# kbd_training.net
KiCad netlist of a schematic drawn in Altium Designer
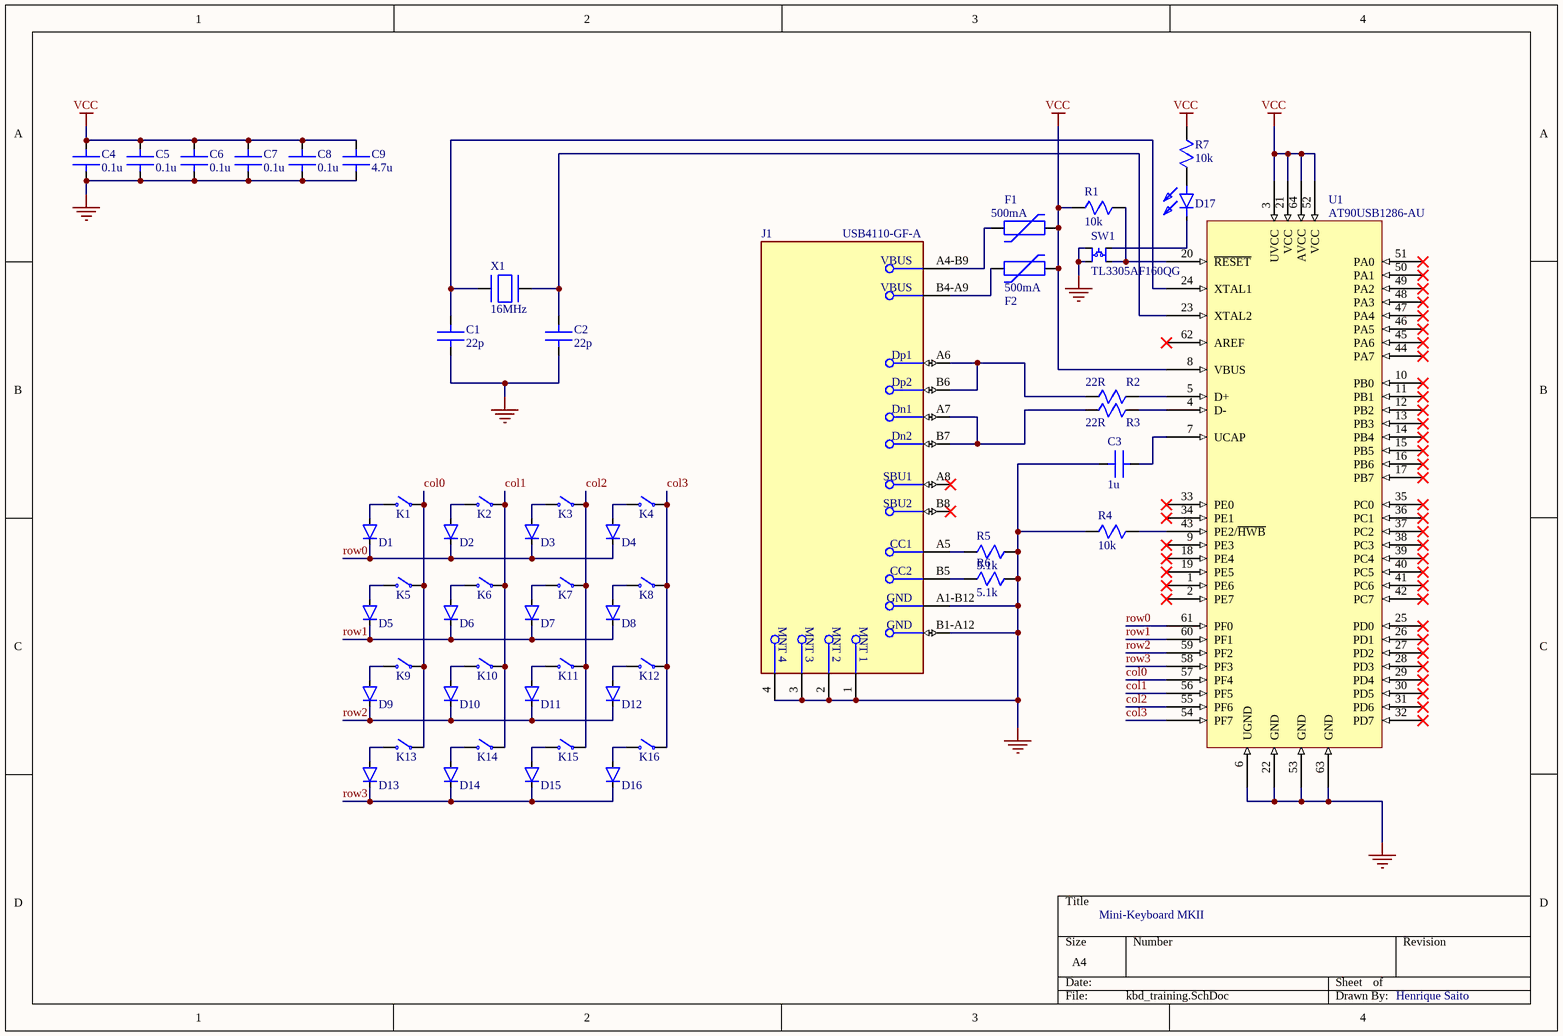
[diagram p0: kbd_training.SchDoc]

(export (version "E")
  (design (tool "Eeschema 10.0.6"))
  (components
    (comp (ref "C1")
      (value "22p")
      (footprint "Cap0805")
      (description "Cap Ceramic 22pF 50V C0G 5% SMD 0805 125C Plastic T/R")
      (fields
        (field (name "MANUFACTURER") "KEMET")
        (field (name "MANUFACTURER PART NUMBER") "C0805C220J5GACTU")
      )
      (libsource (lib "kbd_training_sch_lib") (part "C0805C220J5GACTU"))
    )
    (comp (ref "C2")
      (value "22p")
      (footprint "Cap0805")
      (description "Cap Ceramic 22pF 50V C0G 5% SMD 0805 125C Plastic T/R")
      (fields
        (field (name "MANUFACTURER") "KEMET")
        (field (name "MANUFACTURER PART NUMBER") "C0805C220J5GACTU")
      )
      (libsource (lib "kbd_training_sch_lib") (part "C0805C220J5GACTU"))
    )
    (comp (ref "C3")
      (value "1u")
      (footprint "Cap0805")
      (description "Cap, 1ΜF, 16V, 10%, X7R, 0805")
      (fields
        (field (name "MANUFACTURER") "Wurth Electronics")
        (field (name "MANUFACTURER PART NUMBER") "885012207051")
      )
      (libsource (lib "kbd_training_sch_lib") (part "885012207051"))
    )
    (comp (ref "C4")
      (value "0.1u")
      (footprint "Cap0805")
      (description "Cap Ceramic 0.1uF 50V Y5V -20% to 80% SMD 0805 85C T/R")
      (fields
        (field (name "MANUFACTURER") "Yageo")
        (field (name "MANUFACTURER PART NUMBER") "CC0805ZRY5V9BB104")
      )
      (libsource (lib "kbd_training_sch_lib") (part "CC0805ZRY5V9BB104"))
    )
    (comp (ref "C5")
      (value "0.1u")
      (footprint "Cap0805")
      (description "Cap Ceramic 0.1uF 50V Y5V -20% to 80% SMD 0805 85C T/R")
      (fields
        (field (name "MANUFACTURER") "Yageo")
        (field (name "MANUFACTURER PART NUMBER") "CC0805ZRY5V9BB104")
      )
      (libsource (lib "kbd_training_sch_lib") (part "CC0805ZRY5V9BB104"))
    )
    (comp (ref "C6")
      (value "0.1u")
      (footprint "Cap0805")
      (description "Cap Ceramic 0.1uF 50V Y5V -20% to 80% SMD 0805 85C T/R")
      (fields
        (field (name "MANUFACTURER") "Yageo")
        (field (name "MANUFACTURER PART NUMBER") "CC0805ZRY5V9BB104")
      )
      (libsource (lib "kbd_training_sch_lib") (part "CC0805ZRY5V9BB104"))
    )
    (comp (ref "C7")
      (value "0.1u")
      (footprint "Cap0805")
      (description "Cap Ceramic 0.1uF 50V Y5V -20% to 80% SMD 0805 85C T/R")
      (fields
        (field (name "MANUFACTURER") "Yageo")
        (field (name "MANUFACTURER PART NUMBER") "CC0805ZRY5V9BB104")
      )
      (libsource (lib "kbd_training_sch_lib") (part "CC0805ZRY5V9BB104"))
    )
    (comp (ref "C8")
      (value "0.1u")
      (footprint "Cap0805")
      (description "Cap Ceramic 0.1uF 50V Y5V -20% to 80% SMD 0805 85C T/R")
      (fields
        (field (name "MANUFACTURER") "Yageo")
        (field (name "MANUFACTURER PART NUMBER") "CC0805ZRY5V9BB104")
      )
      (libsource (lib "kbd_training_sch_lib") (part "CC0805ZRY5V9BB104"))
    )
    (comp (ref "C9")
      (value "4.7u")
      (footprint "Cap0805")
      (description "Cap Ceramic 4.7uF 10V X5R 10% SMD 0805 85C T/R")
      (fields
        (field (name "MANUFACTURER") "Samsung")
        (field (name "MANUFACTURER PART NUMBER") "CL21A475KPFNNNE")
      )
      (libsource (lib "kbd_training_sch_lib") (part "CL21A475KPFNNNE"))
    )
    (comp (ref "D1")
      (value "1N4148W-TP")
      (footprint "1N4 diode")
      (description "VR=100V IF=300mA Trr=4ns P=400mW")
      (fields (field (name "MANUFACTURER") "MCC"))
      (libsource (lib "kbd_training_sch_lib") (part "1N4148W-TP"))
    )
    (comp (ref "D2")
      (value "1N4148W-TP")
      (footprint "1N4 diode")
      (description "VR=100V IF=300mA Trr=4ns P=400mW")
      (fields (field (name "MANUFACTURER") "MCC"))
      (libsource (lib "kbd_training_sch_lib") (part "1N4148W-TP"))
    )
    (comp (ref "D3")
      (value "1N4148W-TP")
      (footprint "1N4 diode")
      (description "VR=100V IF=300mA Trr=4ns P=400mW")
      (fields (field (name "MANUFACTURER") "MCC"))
      (libsource (lib "kbd_training_sch_lib") (part "1N4148W-TP"))
    )
    (comp (ref "D4")
      (value "1N4148W-TP")
      (footprint "1N4 diode")
      (description "VR=100V IF=300mA Trr=4ns P=400mW")
      (fields (field (name "MANUFACTURER") "MCC"))
      (libsource (lib "kbd_training_sch_lib") (part "1N4148W-TP"))
    )
    (comp (ref "D5")
      (value "1N4148W-TP")
      (footprint "1N4 diode")
      (description "VR=100V IF=300mA Trr=4ns P=400mW")
      (fields (field (name "MANUFACTURER") "MCC"))
      (libsource (lib "kbd_training_sch_lib") (part "1N4148W-TP"))
    )
    (comp (ref "D6")
      (value "1N4148W-TP")
      (footprint "1N4 diode")
      (description "VR=100V IF=300mA Trr=4ns P=400mW")
      (fields (field (name "MANUFACTURER") "MCC"))
      (libsource (lib "kbd_training_sch_lib") (part "1N4148W-TP"))
    )
    (comp (ref "D7")
      (value "1N4148W-TP")
      (footprint "1N4 diode")
      (description "VR=100V IF=300mA Trr=4ns P=400mW")
      (fields (field (name "MANUFACTURER") "MCC"))
      (libsource (lib "kbd_training_sch_lib") (part "1N4148W-TP"))
    )
    (comp (ref "D8")
      (value "1N4148W-TP")
      (footprint "1N4 diode")
      (description "VR=100V IF=300mA Trr=4ns P=400mW")
      (fields (field (name "MANUFACTURER") "MCC"))
      (libsource (lib "kbd_training_sch_lib") (part "1N4148W-TP"))
    )
    (comp (ref "D9")
      (value "1N4148W-TP")
      (footprint "1N4 diode")
      (description "VR=100V IF=300mA Trr=4ns P=400mW")
      (fields (field (name "MANUFACTURER") "MCC"))
      (libsource (lib "kbd_training_sch_lib") (part "1N4148W-TP"))
    )
    (comp (ref "D10")
      (value "1N4148W-TP")
      (footprint "1N4 diode")
      (description "VR=100V IF=300mA Trr=4ns P=400mW")
      (fields (field (name "MANUFACTURER") "MCC"))
      (libsource (lib "kbd_training_sch_lib") (part "1N4148W-TP"))
    )
    (comp (ref "D11")
      (value "1N4148W-TP")
      (footprint "1N4 diode")
      (description "VR=100V IF=300mA Trr=4ns P=400mW")
      (fields (field (name "MANUFACTURER") "MCC"))
      (libsource (lib "kbd_training_sch_lib") (part "1N4148W-TP"))
    )
    (comp (ref "D12")
      (value "1N4148W-TP")
      (footprint "1N4 diode")
      (description "VR=100V IF=300mA Trr=4ns P=400mW")
      (fields (field (name "MANUFACTURER") "MCC"))
      (libsource (lib "kbd_training_sch_lib") (part "1N4148W-TP"))
    )
    (comp (ref "D13")
      (value "1N4148W-TP")
      (footprint "1N4 diode")
      (description "VR=100V IF=300mA Trr=4ns P=400mW")
      (fields (field (name "MANUFACTURER") "MCC"))
      (libsource (lib "kbd_training_sch_lib") (part "1N4148W-TP"))
    )
    (comp (ref "D14")
      (value "1N4148W-TP")
      (footprint "1N4 diode")
      (description "VR=100V IF=300mA Trr=4ns P=400mW")
      (fields (field (name "MANUFACTURER") "MCC"))
      (libsource (lib "kbd_training_sch_lib") (part "1N4148W-TP"))
    )
    (comp (ref "D15")
      (value "1N4148W-TP")
      (footprint "1N4 diode")
      (description "VR=100V IF=300mA Trr=4ns P=400mW")
      (fields (field (name "MANUFACTURER") "MCC"))
      (libsource (lib "kbd_training_sch_lib") (part "1N4148W-TP"))
    )
    (comp (ref "D16")
      (value "1N4148W-TP")
      (footprint "1N4 diode")
      (description "VR=100V IF=300mA Trr=4ns P=400mW")
      (fields (field (name "MANUFACTURER") "MCC"))
      (libsource (lib "kbd_training_sch_lib") (part "1N4148W-TP"))
    )
    (comp (ref "D17")
      (value "WP5603SIDLK/SD/J3")
      (footprint "MT5470EUR")
      (description "LED Uni-Color Hyper Red 640nm 2-Pin Bulk")
      (fields (field (name "MANUFACTURER") "Kingbright"))
      (libsource (lib "kbd_training_sch_lib") (part "WP5603SIDLK/SD/J3"))
    )
    (comp (ref "F1")
      (value "500mA")
      (footprint "FUS0603")
      (description "Fuse Chip Fast Acting 0.5A 32V SMD Solder Pad 0402 1 X 0.5 X 0.39mm T/R UL/cUL")
      (fields
        (field (name "MANUFACTURER") "Panasonic")
        (field (name "MANUFACTURER PART NUMBER") "ERBRD0R50X")
      )
      (libsource (lib "kbd_training_sch_lib") (part "ERBRD0R50X"))
    )
    (comp (ref "F2")
      (value "500mA")
      (footprint "FUS0603")
      (description "Fuse Chip Fast Acting 0.5A 32V SMD Solder Pad 0402 1 X 0.5 X 0.39mm T/R UL/cUL")
      (fields
        (field (name "MANUFACTURER") "Panasonic")
        (field (name "MANUFACTURER PART NUMBER") "ERBRD0R50X")
      )
      (libsource (lib "kbd_training_sch_lib") (part "ERBRD0R50X"))
    )
    (comp (ref "J1")
      (value "USB4110-GF-A")
      (footprint "GCT_USB4110-GF-A_REVB")
      (description "CONN USB 2.0 TYPE-C R/A SMT")
      (fields
        (field (name "OCTOPART") "https://octopart.com/usb4110-gf-a-gct-103941985")
        (field (name "MANUFACTURER") "GCT")
      )
      (libsource (lib "kbd_training_sch_lib") (part "CMP-245163-000002-1"))
    )
    (comp (ref "K1")
      (value "MX1A-11NN")
      (footprint "CHERRY_MX1A-11NN_SWITCH")
      (description "Switch Key N.O. SPST 0.01A 12VAC 12VDC 0.58N PC Pins 50000000Cycles Thru-Hole")
      (fields (field (name "MANUFACTURER") "Cherry"))
      (libsource (lib "kbd_training_sch_lib") (part "MX1A-11NN"))
    )
    (comp (ref "K2")
      (value "MX1A-11NN")
      (footprint "CHERRY_MX1A-11NN_SWITCH")
      (description "Switch Key N.O. SPST 0.01A 12VAC 12VDC 0.58N PC Pins 50000000Cycles Thru-Hole")
      (fields (field (name "MANUFACTURER") "Cherry"))
      (libsource (lib "kbd_training_sch_lib") (part "MX1A-11NN"))
    )
    (comp (ref "K3")
      (value "MX1A-11NN")
      (footprint "CHERRY_MX1A-11NN_SWITCH")
      (description "Switch Key N.O. SPST 0.01A 12VAC 12VDC 0.58N PC Pins 50000000Cycles Thru-Hole")
      (fields (field (name "MANUFACTURER") "Cherry"))
      (libsource (lib "kbd_training_sch_lib") (part "MX1A-11NN"))
    )
    (comp (ref "K4")
      (value "MX1A-11NN")
      (footprint "CHERRY_MX1A-11NN_SWITCH")
      (description "Switch Key N.O. SPST 0.01A 12VAC 12VDC 0.58N PC Pins 50000000Cycles Thru-Hole")
      (fields (field (name "MANUFACTURER") "Cherry"))
      (libsource (lib "kbd_training_sch_lib") (part "MX1A-11NN"))
    )
    (comp (ref "K5")
      (value "MX1A-11NN")
      (footprint "CHERRY_MX1A-11NN_SWITCH")
      (description "Switch Key N.O. SPST 0.01A 12VAC 12VDC 0.58N PC Pins 50000000Cycles Thru-Hole")
      (fields (field (name "MANUFACTURER") "Cherry"))
      (libsource (lib "kbd_training_sch_lib") (part "MX1A-11NN"))
    )
    (comp (ref "K6")
      (value "MX1A-11NN")
      (footprint "CHERRY_MX1A-11NN_SWITCH")
      (description "Switch Key N.O. SPST 0.01A 12VAC 12VDC 0.58N PC Pins 50000000Cycles Thru-Hole")
      (fields (field (name "MANUFACTURER") "Cherry"))
      (libsource (lib "kbd_training_sch_lib") (part "MX1A-11NN"))
    )
    (comp (ref "K7")
      (value "MX1A-11NN")
      (footprint "CHERRY_MX1A-11NN_SWITCH")
      (description "Switch Key N.O. SPST 0.01A 12VAC 12VDC 0.58N PC Pins 50000000Cycles Thru-Hole")
      (fields (field (name "MANUFACTURER") "Cherry"))
      (libsource (lib "kbd_training_sch_lib") (part "MX1A-11NN"))
    )
    (comp (ref "K8")
      (value "MX1A-11NN")
      (footprint "CHERRY_MX1A-11NN_SWITCH")
      (description "Switch Key N.O. SPST 0.01A 12VAC 12VDC 0.58N PC Pins 50000000Cycles Thru-Hole")
      (fields (field (name "MANUFACTURER") "Cherry"))
      (libsource (lib "kbd_training_sch_lib") (part "MX1A-11NN"))
    )
    (comp (ref "K9")
      (value "MX1A-11NN")
      (footprint "CHERRY_MX1A-11NN_SWITCH")
      (description "Switch Key N.O. SPST 0.01A 12VAC 12VDC 0.58N PC Pins 50000000Cycles Thru-Hole")
      (fields (field (name "MANUFACTURER") "Cherry"))
      (libsource (lib "kbd_training_sch_lib") (part "MX1A-11NN"))
    )
    (comp (ref "K10")
      (value "MX1A-11NN")
      (footprint "CHERRY_MX1A-11NN_SWITCH")
      (description "Switch Key N.O. SPST 0.01A 12VAC 12VDC 0.58N PC Pins 50000000Cycles Thru-Hole")
      (fields (field (name "MANUFACTURER") "Cherry"))
      (libsource (lib "kbd_training_sch_lib") (part "MX1A-11NN"))
    )
    (comp (ref "K11")
      (value "MX1A-11NN")
      (footprint "CHERRY_MX1A-11NN_SWITCH")
      (description "Switch Key N.O. SPST 0.01A 12VAC 12VDC 0.58N PC Pins 50000000Cycles Thru-Hole")
      (fields (field (name "MANUFACTURER") "Cherry"))
      (libsource (lib "kbd_training_sch_lib") (part "MX1A-11NN"))
    )
    (comp (ref "K12")
      (value "MX1A-11NN")
      (footprint "CHERRY_MX1A-11NN_SWITCH")
      (description "Switch Key N.O. SPST 0.01A 12VAC 12VDC 0.58N PC Pins 50000000Cycles Thru-Hole")
      (fields (field (name "MANUFACTURER") "Cherry"))
      (libsource (lib "kbd_training_sch_lib") (part "MX1A-11NN"))
    )
    (comp (ref "K13")
      (value "MX1A-11NN")
      (footprint "CHERRY_MX1A-11NN_SWITCH")
      (description "Switch Key N.O. SPST 0.01A 12VAC 12VDC 0.58N PC Pins 50000000Cycles Thru-Hole")
      (fields (field (name "MANUFACTURER") "Cherry"))
      (libsource (lib "kbd_training_sch_lib") (part "MX1A-11NN"))
    )
    (comp (ref "K14")
      (value "MX1A-11NN")
      (footprint "CHERRY_MX1A-11NN_SWITCH")
      (description "Switch Key N.O. SPST 0.01A 12VAC 12VDC 0.58N PC Pins 50000000Cycles Thru-Hole")
      (fields (field (name "MANUFACTURER") "Cherry"))
      (libsource (lib "kbd_training_sch_lib") (part "MX1A-11NN"))
    )
    (comp (ref "K15")
      (value "MX1A-11NN")
      (footprint "CHERRY_MX1A-11NN_SWITCH")
      (description "Switch Key N.O. SPST 0.01A 12VAC 12VDC 0.58N PC Pins 50000000Cycles Thru-Hole")
      (fields (field (name "MANUFACTURER") "Cherry"))
      (libsource (lib "kbd_training_sch_lib") (part "MX1A-11NN"))
    )
    (comp (ref "K16")
      (value "MX1A-11NN")
      (footprint "CHERRY_MX1A-11NN_SWITCH")
      (description "Switch Key N.O. SPST 0.01A 12VAC 12VDC 0.58N PC Pins 50000000Cycles Thru-Hole")
      (fields (field (name "MANUFACTURER") "Cherry"))
      (libsource (lib "kbd_training_sch_lib") (part "MX1A-11NN"))
    )
    (comp (ref "R1")
      (value "10k")
      (footprint "Res0805")
      (description "Res Thick Film 0805 10K Ohm 5% 0.125W(1/8W) ±200ppm/C Pad SMD Automotive T/R")
      (fields
        (field (name "MANUFACTURER") "Stackpole Electronics")
        (field (name "MANUFACTURER PART NUMBER") "RMCF0805JT10K0")
      )
      (libsource (lib "kbd_training_sch_lib") (part "RMCF0805JT10K0"))
    )
    (comp (ref "R2")
      (value "22R")
      (footprint "Res0805")
      (description "Res Thick Film 0805 22 Ohm 1% 1/8W 100ppm/C Molded SMD SMD Paper Tape on Plastic Reel")
      (fields
        (field (name "MANUFACTURER") "Bourns")
        (field (name "MANUFACTURER PART NUMBER") "CR0805-FX-22R0ELF")
      )
      (libsource (lib "kbd_training_sch_lib") (part "CR0805-FX-22R0ELF"))
    )
    (comp (ref "R3")
      (value "22R")
      (footprint "Res0805")
      (description "Res Thick Film 0805 22 Ohm 1% 1/8W 100ppm/C Molded SMD SMD Paper Tape on Plastic Reel")
      (fields
        (field (name "MANUFACTURER") "Bourns")
        (field (name "MANUFACTURER PART NUMBER") "CR0805-FX-22R0ELF")
      )
      (libsource (lib "kbd_training_sch_lib") (part "CR0805-FX-22R0ELF"))
    )
    (comp (ref "R4")
      (value "10k")
      (footprint "Res0805")
      (description "Res Thick Film 0805 10K Ohm 5% 0.125W(1/8W) ±200ppm/C Pad SMD Automotive T/R")
      (fields
        (field (name "MANUFACTURER") "Stackpole Electronics")
        (field (name "MANUFACTURER PART NUMBER") "RMCF0805JT10K0")
      )
      (libsource (lib "kbd_training_sch_lib") (part "RMCF0805JT10K0"))
    )
    (comp (ref "R5")
      (value "5.1k")
      (footprint "Res0805")
      (description "Res Thick Film 0805 5.1K Ohm 5% 2/5W ±200ppm/°C Molded SMD SMD Paper T/R")
      (fields (field (name "MANUFACTURER") "Rohm") (field (name "MANUFACTURER PART NUMBER") "ESR10EZPJ512"))
      (libsource (lib "kbd_training_sch_lib") (part "ESR10EZPJ512"))
    )
    (comp (ref "R6")
      (value "5.1k")
      (footprint "Res0805")
      (description "Res Thick Film 0805 5.1K Ohm 5% 2/5W ±200ppm/°C Molded SMD SMD Paper T/R")
      (fields (field (name "MANUFACTURER") "Rohm") (field (name "MANUFACTURER PART NUMBER") "ESR10EZPJ512"))
      (libsource (lib "kbd_training_sch_lib") (part "ESR10EZPJ512"))
    )
    (comp (ref "R7")
      (value "10k")
      (footprint "Res0805")
      (description "Res Thick Film 0805 10K Ohm 5% 0.125W(1/8W) ±200ppm/C Pad SMD Automotive T/R")
      (fields
        (field (name "MANUFACTURER") "Stackpole Electronics")
        (field (name "MANUFACTURER PART NUMBER") "RMCF0805JT10K0")
      )
      (libsource (lib "kbd_training_sch_lib") (part "RMCF0805JT10K0"))
    )
    (comp (ref "SW1")
      (value "TL3305AF160QG")
      (footprint "TL3305 SW")
      (description "TL3305A Series SPST 12 V 4.5 x 4.5 mm 160 gf Top Actuated SMT Tactile Switch")
      (fields (field (name "MANUFACTURER") "E-Switch"))
      (libsource (lib "kbd_training_sch_lib") (part "TL3305AF160QG"))
    )
    (comp (ref "U1")
      (value "AT90USB1286-AU")
      (footprint "QFP80P1600X1600X120-64N")
      (description "AT90 Series 128 KB Flash 8 kB SRAM 16 MHz 8-Bit Microcontroller - TQFP-64")
      (fields (field (name "MANUFACTURER") "Microchip"))
      (libsource (lib "kbd_training_sch_lib") (part "AT90USB1286-AU"))
    )
    (comp (ref "X1")
      (value "16MHz")
      (footprint "xtal-m403")
      (description "Crystal 16MHz ±30ppm (Tol) ±50ppm (Stability) 18pF FUND 80Ohm 4-Pin SMD T/R")
      (fields (field (name "MANUFACTURER") "CTS") (field (name "MANUFACTURER PART NUMBER") "403I35D16M00000"))
      (libsource (lib "kbd_training_sch_lib") (part "403I35D16M00000"))
    )
  )
  (nets
    (net (code "1") (name "/col0") (class "Default")
      (node (ref "K1") (pin "2") (pinfunction "2_2") (pintype "passive"))
      (node (ref "K13") (pin "2") (pinfunction "2_2") (pintype "passive"))
      (node (ref "K5") (pin "2") (pinfunction "2_2") (pintype "passive"))
      (node (ref "K9") (pin "2") (pinfunction "2_2") (pintype "passive"))
      (node (ref "U1") (pin "57") (pinfunction "PF4_57") (pintype "input"))
    )
    (net (code "2") (name "/col1") (class "Default")
      (node (ref "K10") (pin "2") (pinfunction "2_2") (pintype "passive"))
      (node (ref "K14") (pin "2") (pinfunction "2_2") (pintype "passive"))
      (node (ref "K2") (pin "2") (pinfunction "2_2") (pintype "passive"))
      (node (ref "K6") (pin "2") (pinfunction "2_2") (pintype "passive"))
      (node (ref "U1") (pin "56") (pinfunction "PF5_56") (pintype "input"))
    )
    (net (code "3") (name "/col2") (class "Default")
      (node (ref "K11") (pin "2") (pinfunction "2_2") (pintype "passive"))
      (node (ref "K15") (pin "2") (pinfunction "2_2") (pintype "passive"))
      (node (ref "K3") (pin "2") (pinfunction "2_2") (pintype "passive"))
      (node (ref "K7") (pin "2") (pinfunction "2_2") (pintype "passive"))
      (node (ref "U1") (pin "55") (pinfunction "PF6_55") (pintype "input"))
    )
    (net (code "4") (name "/col3") (class "Default")
      (node (ref "K12") (pin "2") (pinfunction "2_2") (pintype "passive"))
      (node (ref "K16") (pin "2") (pinfunction "2_2") (pintype "passive"))
      (node (ref "K4") (pin "2") (pinfunction "2_2") (pintype "passive"))
      (node (ref "K8") (pin "2") (pinfunction "2_2") (pintype "passive"))
      (node (ref "U1") (pin "54") (pinfunction "PF7_54") (pintype "input"))
    )
    (net (code "5") (name "/row0") (class "Default")
      (node (ref "D1") (pin "2") (pinfunction "2_2") (pintype "passive"))
      (node (ref "D2") (pin "2") (pinfunction "2_2") (pintype "passive"))
      (node (ref "D3") (pin "2") (pinfunction "2_2") (pintype "passive"))
      (node (ref "D4") (pin "2") (pinfunction "2_2") (pintype "passive"))
      (node (ref "U1") (pin "61") (pinfunction "PF0_61") (pintype "input"))
    )
    (net (code "6") (name "/row1") (class "Default")
      (node (ref "D5") (pin "2") (pinfunction "2_2") (pintype "passive"))
      (node (ref "D6") (pin "2") (pinfunction "2_2") (pintype "passive"))
      (node (ref "D7") (pin "2") (pinfunction "2_2") (pintype "passive"))
      (node (ref "D8") (pin "2") (pinfunction "2_2") (pintype "passive"))
      (node (ref "U1") (pin "60") (pinfunction "PF1_60") (pintype "input"))
    )
    (net (code "7") (name "/row2") (class "Default")
      (node (ref "D10") (pin "2") (pinfunction "2_2") (pintype "passive"))
      (node (ref "D11") (pin "2") (pinfunction "2_2") (pintype "passive"))
      (node (ref "D12") (pin "2") (pinfunction "2_2") (pintype "passive"))
      (node (ref "D9") (pin "2") (pinfunction "2_2") (pintype "passive"))
      (node (ref "U1") (pin "59") (pinfunction "PF2_59") (pintype "input"))
    )
    (net (code "8") (name "/row3") (class "Default")
      (node (ref "D13") (pin "2") (pinfunction "2_2") (pintype "passive"))
      (node (ref "D14") (pin "2") (pinfunction "2_2") (pintype "passive"))
      (node (ref "D15") (pin "2") (pinfunction "2_2") (pintype "passive"))
      (node (ref "D16") (pin "2") (pinfunction "2_2") (pintype "passive"))
      (node (ref "U1") (pin "58") (pinfunction "PF3_58") (pintype "input"))
    )
    (net (code "9") (name "GND") (class "Default")
      (node (ref "C1") (pin "2") (pintype "passive"))
      (node (ref "C2") (pin "2") (pintype "passive"))
      (node (ref "C3") (pin "1") (pinfunction "1_1") (pintype "passive"))
      (node (ref "C4") (pin "1") (pinfunction "1_1") (pintype "passive"))
      (node (ref "C5") (pin "1") (pinfunction "1_1") (pintype "passive"))
      (node (ref "C6") (pin "1") (pinfunction "1_1") (pintype "passive"))
      (node (ref "C7") (pin "1") (pinfunction "1_1") (pintype "passive"))
      (node (ref "C8") (pin "1") (pinfunction "1_1") (pintype "passive"))
      (node (ref "C9") (pin "1") (pinfunction "1_1") (pintype "passive"))
      (node (ref "J1") (pin "1") (pinfunction "MNT_1_1") (pintype "passive"))
      (node (ref "J1") (pin "2") (pinfunction "MNT_2_2") (pintype "passive"))
      (node (ref "J1") (pin "3") (pinfunction "MNT_3_3") (pintype "passive"))
      (node (ref "J1") (pin "4") (pinfunction "MNT_4_4") (pintype "passive"))
      (node (ref "J1") (pin "A1-B12") (pinfunction "GND_A1-B12") (pintype "passive"))
      (node (ref "J1") (pin "B1-A12") (pinfunction "GND_B1-A12") (pintype "bidirectional"))
      (node (ref "R4") (pin "1") (pinfunction "1_1") (pintype "passive"))
      (node (ref "R5") (pin "2") (pinfunction "2_2") (pintype "passive"))
      (node (ref "R6") (pin "2") (pinfunction "2_2") (pintype "passive"))
      (node (ref "SW1") (pin "3") (pinfunction "3_3") (pintype "passive"))
      (node (ref "SW1") (pin "4") (pinfunction "4_4") (pintype "passive"))
      (node (ref "U1") (pin "22") (pinfunction "GND_22") (pintype "input"))
      (node (ref "U1") (pin "53") (pinfunction "GND_53") (pintype "input"))
      (node (ref "U1") (pin "6") (pinfunction "UGND_6") (pintype "input"))
      (node (ref "U1") (pin "63") (pinfunction "GND_63") (pintype "input"))
    )
    (net (code "10") (name "Net-(D1-Pad1)") (class "Default")
      (node (ref "D1") (pin "1") (pinfunction "1_1") (pintype "passive"))
      (node (ref "K1") (pin "1") (pinfunction "1_1") (pintype "passive"))
    )
    (net (code "11") (name "Net-(D2-Pad1)") (class "Default")
      (node (ref "D2") (pin "1") (pinfunction "1_1") (pintype "passive"))
      (node (ref "K2") (pin "1") (pinfunction "1_1") (pintype "passive"))
    )
    (net (code "12") (name "Net-(D3-Pad1)") (class "Default")
      (node (ref "D3") (pin "1") (pinfunction "1_1") (pintype "passive"))
      (node (ref "K3") (pin "1") (pinfunction "1_1") (pintype "passive"))
    )
    (net (code "13") (name "Net-(D4-Pad1)") (class "Default")
      (node (ref "D4") (pin "1") (pinfunction "1_1") (pintype "passive"))
      (node (ref "K4") (pin "1") (pinfunction "1_1") (pintype "passive"))
    )
    (net (code "14") (name "Net-(D5-Pad1)") (class "Default")
      (node (ref "D5") (pin "1") (pinfunction "1_1") (pintype "passive"))
      (node (ref "K5") (pin "1") (pinfunction "1_1") (pintype "passive"))
    )
    (net (code "15") (name "Net-(D6-Pad1)") (class "Default")
      (node (ref "D6") (pin "1") (pinfunction "1_1") (pintype "passive"))
      (node (ref "K6") (pin "1") (pinfunction "1_1") (pintype "passive"))
    )
    (net (code "16") (name "Net-(D7-Pad1)") (class "Default")
      (node (ref "D7") (pin "1") (pinfunction "1_1") (pintype "passive"))
      (node (ref "K7") (pin "1") (pinfunction "1_1") (pintype "passive"))
    )
    (net (code "17") (name "Net-(D8-Pad1)") (class "Default")
      (node (ref "D8") (pin "1") (pinfunction "1_1") (pintype "passive"))
      (node (ref "K8") (pin "1") (pinfunction "1_1") (pintype "passive"))
    )
    (net (code "18") (name "Net-(D9-Pad1)") (class "Default")
      (node (ref "D9") (pin "1") (pinfunction "1_1") (pintype "passive"))
      (node (ref "K9") (pin "1") (pinfunction "1_1") (pintype "passive"))
    )
    (net (code "19") (name "Net-(D10-Pad1)") (class "Default")
      (node (ref "D10") (pin "1") (pinfunction "1_1") (pintype "passive"))
      (node (ref "K10") (pin "1") (pinfunction "1_1") (pintype "passive"))
    )
    (net (code "20") (name "Net-(D11-Pad1)") (class "Default")
      (node (ref "D11") (pin "1") (pinfunction "1_1") (pintype "passive"))
      (node (ref "K11") (pin "1") (pinfunction "1_1") (pintype "passive"))
    )
    (net (code "21") (name "Net-(D12-Pad1)") (class "Default")
      (node (ref "D12") (pin "1") (pinfunction "1_1") (pintype "passive"))
      (node (ref "K12") (pin "1") (pinfunction "1_1") (pintype "passive"))
    )
    (net (code "22") (name "Net-(D13-Pad1)") (class "Default")
      (node (ref "D13") (pin "1") (pinfunction "1_1") (pintype "passive"))
      (node (ref "K13") (pin "1") (pinfunction "1_1") (pintype "passive"))
    )
    (net (code "23") (name "Net-(D14-Pad1)") (class "Default")
      (node (ref "D14") (pin "1") (pinfunction "1_1") (pintype "passive"))
      (node (ref "K14") (pin "1") (pinfunction "1_1") (pintype "passive"))
    )
    (net (code "24") (name "Net-(D15-Pad1)") (class "Default")
      (node (ref "D15") (pin "1") (pinfunction "1_1") (pintype "passive"))
      (node (ref "K15") (pin "1") (pinfunction "1_1") (pintype "passive"))
    )
    (net (code "25") (name "Net-(D16-Pad1)") (class "Default")
      (node (ref "D16") (pin "1") (pinfunction "1_1") (pintype "passive"))
      (node (ref "K16") (pin "1") (pinfunction "1_1") (pintype "passive"))
    )
    (net (code "26") (name "Net-(D17-Pad1)") (class "Default")
      (node (ref "D17") (pin "1") (pinfunction "1_1") (pintype "passive"))
      (node (ref "SW1") (pin "2") (pinfunction "2_2") (pintype "passive"))
    )
    (net (code "27") (name "Net-(D17-Pad2)") (class "Default")
      (node (ref "D17") (pin "2") (pinfunction "2_2") (pintype "passive"))
      (node (ref "R7") (pin "1") (pinfunction "1_1") (pintype "passive"))
    )
    (net (code "28") (name "Net-(F1-Pad1)") (class "Default")
      (node (ref "F1") (pin "1") (pinfunction "1_1") (pintype "passive"))
      (node (ref "J1") (pin "A4-B9") (pinfunction "VBUS_A4-B9") (pintype "power_in"))
    )
    (net (code "29") (name "Net-(F2-Pad1)") (class "Default")
      (node (ref "F2") (pin "1") (pinfunction "1_1") (pintype "passive"))
      (node (ref "J1") (pin "B4-A9") (pinfunction "VBUS_B4-A9") (pintype "power_in"))
    )
    (net (code "30") (name "Net-(J1-CC1)") (class "Default")
      (node (ref "J1") (pin "A5") (pinfunction "CC1_A5") (pintype "power_in"))
      (node (ref "R5") (pin "1") (pinfunction "1_1") (pintype "passive"))
    )
    (net (code "31") (name "Net-(J1-CC2)") (class "Default")
      (node (ref "J1") (pin "B5") (pinfunction "CC2_B5") (pintype "power_in"))
      (node (ref "R6") (pin "1") (pinfunction "1_1") (pintype "passive"))
    )
    (net (code "32") (name "Net-(J1-Dn1)") (class "Default")
      (node (ref "J1") (pin "A7") (pinfunction "Dn1_A7") (pintype "bidirectional"))
      (node (ref "J1") (pin "B7") (pinfunction "Dn2_B7") (pintype "bidirectional"))
      (node (ref "R3") (pin "1") (pinfunction "1_1") (pintype "passive"))
    )
    (net (code "33") (name "Net-(J1-Dp1)") (class "Default")
      (node (ref "J1") (pin "A6") (pinfunction "Dp1_A6") (pintype "bidirectional"))
      (node (ref "J1") (pin "B6") (pinfunction "Dp2_B6") (pintype "bidirectional"))
      (node (ref "R2") (pin "1") (pinfunction "1_1") (pintype "passive"))
    )
    (net (code "34") (name "Net-(U1-D+)") (class "Default")
      (node (ref "R2") (pin "2") (pinfunction "2_2") (pintype "passive"))
      (node (ref "U1") (pin "5") (pinfunction "D+_5") (pintype "input"))
    )
    (net (code "35") (name "Net-(U1-D-)") (class "Default")
      (node (ref "R3") (pin "2") (pinfunction "2_2") (pintype "passive"))
      (node (ref "U1") (pin "4") (pinfunction "D-_4") (pintype "input"))
    )
    (net (code "36") (name "Net-(U1-PE2{slash}~{HWB})") (class "Default")
      (node (ref "R4") (pin "2") (pinfunction "2_2") (pintype "passive"))
      (node (ref "U1") (pin "43") (pinfunction "PE2/~{HWB}_43") (pintype "input"))
    )
    (net (code "37") (name "Net-(U1-UCAP)") (class "Default")
      (node (ref "C3") (pin "2") (pintype "passive"))
      (node (ref "U1") (pin "7") (pinfunction "UCAP_7") (pintype "input"))
    )
    (net (code "38") (name "Net-(U1-XTAL1)") (class "Default")
      (node (ref "C1") (pin "1") (pinfunction "1_1") (pintype "passive"))
      (node (ref "U1") (pin "24") (pinfunction "XTAL1_24") (pintype "input"))
      (node (ref "X1") (pin "1") (pinfunction "1_1") (pintype "passive"))
    )
    (net (code "39") (name "Net-(U1-XTAL2)") (class "Default")
      (node (ref "C2") (pin "1") (pinfunction "1_1") (pintype "passive"))
      (node (ref "U1") (pin "23") (pinfunction "XTAL2_23") (pintype "input"))
      (node (ref "X1") (pin "3") (pinfunction "3_3") (pintype "passive"))
    )
    (net (code "40") (name "Net-(U1-~{RESET})") (class "Default")
      (node (ref "R1") (pin "2") (pinfunction "2_2") (pintype "passive"))
      (node (ref "SW1") (pin "1") (pinfunction "1_1") (pintype "passive"))
      (node (ref "U1") (pin "20") (pinfunction "~{RESET}_20") (pintype "input"))
    )
    (net (code "41") (name "VCC") (class "Default")
      (node (ref "C4") (pin "2") (pintype "passive"))
      (node (ref "C5") (pin "2") (pintype "passive"))
      (node (ref "C6") (pin "2") (pintype "passive"))
      (node (ref "C7") (pin "2") (pintype "passive"))
      (node (ref "C8") (pin "2") (pintype "passive"))
      (node (ref "C9") (pin "2") (pintype "passive"))
      (node (ref "F1") (pin "2") (pinfunction "2_2") (pintype "passive"))
      (node (ref "F2") (pin "2") (pinfunction "2_2") (pintype "passive"))
      (node (ref "R1") (pin "1") (pinfunction "1_1") (pintype "passive"))
      (node (ref "R7") (pin "2") (pinfunction "2_2") (pintype "passive"))
      (node (ref "U1") (pin "21") (pinfunction "VCC_21") (pintype "input"))
      (node (ref "U1") (pin "3") (pinfunction "UVCC_3") (pintype "input"))
      (node (ref "U1") (pin "52") (pinfunction "VCC_52") (pintype "input"))
      (node (ref "U1") (pin "64") (pinfunction "AVCC_64") (pintype "input"))
      (node (ref "U1") (pin "8") (pinfunction "VBUS_8") (pintype "input"))
    )
    (net (code "42") (name "unconnected-(J1-SBU1-PadA8)") (class "Default")
      (node (ref "J1") (pin "A8") (pinfunction "SBU1_A8") (pintype "bidirectional+no_connect"))
    )
    (net (code "43") (name "unconnected-(J1-SBU2-PadB8)") (class "Default")
      (node (ref "J1") (pin "B8") (pinfunction "SBU2_B8") (pintype "bidirectional+no_connect"))
    )
    (net (code "44") (name "unconnected-(U1-AREF-Pad62)") (class "Default")
      (node (ref "U1") (pin "62") (pinfunction "AREF_62") (pintype "input+no_connect"))
    )
    (net (code "45") (name "unconnected-(U1-PA0-Pad51)") (class "Default")
      (node (ref "U1") (pin "51") (pinfunction "PA0_51") (pintype "input+no_connect"))
    )
    (net (code "46") (name "unconnected-(U1-PA1-Pad50)") (class "Default")
      (node (ref "U1") (pin "50") (pinfunction "PA1_50") (pintype "input+no_connect"))
    )
    (net (code "47") (name "unconnected-(U1-PA2-Pad49)") (class "Default")
      (node (ref "U1") (pin "49") (pinfunction "PA2_49") (pintype "input+no_connect"))
    )
    (net (code "48") (name "unconnected-(U1-PA3-Pad48)") (class "Default")
      (node (ref "U1") (pin "48") (pinfunction "PA3_48") (pintype "input+no_connect"))
    )
    (net (code "49") (name "unconnected-(U1-PA4-Pad47)") (class "Default")
      (node (ref "U1") (pin "47") (pinfunction "PA4_47") (pintype "input+no_connect"))
    )
    (net (code "50") (name "unconnected-(U1-PA5-Pad46)") (class "Default")
      (node (ref "U1") (pin "46") (pinfunction "PA5_46") (pintype "input+no_connect"))
    )
    (net (code "51") (name "unconnected-(U1-PA6-Pad45)") (class "Default")
      (node (ref "U1") (pin "45") (pinfunction "PA6_45") (pintype "input+no_connect"))
    )
    (net (code "52") (name "unconnected-(U1-PA7-Pad44)") (class "Default")
      (node (ref "U1") (pin "44") (pinfunction "PA7_44") (pintype "input+no_connect"))
    )
    (net (code "53") (name "unconnected-(U1-PB0-Pad10)") (class "Default")
      (node (ref "U1") (pin "10") (pinfunction "PB0_10") (pintype "input+no_connect"))
    )
    (net (code "54") (name "unconnected-(U1-PB1-Pad11)") (class "Default")
      (node (ref "U1") (pin "11") (pinfunction "PB1_11") (pintype "input+no_connect"))
    )
    (net (code "55") (name "unconnected-(U1-PB2-Pad12)") (class "Default")
      (node (ref "U1") (pin "12") (pinfunction "PB2_12") (pintype "input+no_connect"))
    )
    (net (code "56") (name "unconnected-(U1-PB3-Pad13)") (class "Default")
      (node (ref "U1") (pin "13") (pinfunction "PB3_13") (pintype "input+no_connect"))
    )
    (net (code "57") (name "unconnected-(U1-PB4-Pad14)") (class "Default")
      (node (ref "U1") (pin "14") (pinfunction "PB4_14") (pintype "input+no_connect"))
    )
    (net (code "58") (name "unconnected-(U1-PB5-Pad15)") (class "Default")
      (node (ref "U1") (pin "15") (pinfunction "PB5_15") (pintype "input+no_connect"))
    )
    (net (code "59") (name "unconnected-(U1-PB6-Pad16)") (class "Default")
      (node (ref "U1") (pin "16") (pinfunction "PB6_16") (pintype "input+no_connect"))
    )
    (net (code "60") (name "unconnected-(U1-PB7-Pad17)") (class "Default")
      (node (ref "U1") (pin "17") (pinfunction "PB7_17") (pintype "input+no_connect"))
    )
    (net (code "61") (name "unconnected-(U1-PC0-Pad35)") (class "Default")
      (node (ref "U1") (pin "35") (pinfunction "PC0_35") (pintype "input+no_connect"))
    )
    (net (code "62") (name "unconnected-(U1-PC1-Pad36)") (class "Default")
      (node (ref "U1") (pin "36") (pinfunction "PC1_36") (pintype "input+no_connect"))
    )
    (net (code "63") (name "unconnected-(U1-PC2-Pad37)") (class "Default")
      (node (ref "U1") (pin "37") (pinfunction "PC2_37") (pintype "input+no_connect"))
    )
    (net (code "64") (name "unconnected-(U1-PC3-Pad38)") (class "Default")
      (node (ref "U1") (pin "38") (pinfunction "PC3_38") (pintype "input+no_connect"))
    )
    (net (code "65") (name "unconnected-(U1-PC4-Pad39)") (class "Default")
      (node (ref "U1") (pin "39") (pinfunction "PC4_39") (pintype "input+no_connect"))
    )
    (net (code "66") (name "unconnected-(U1-PC5-Pad40)") (class "Default")
      (node (ref "U1") (pin "40") (pinfunction "PC5_40") (pintype "input+no_connect"))
    )
    (net (code "67") (name "unconnected-(U1-PC6-Pad41)") (class "Default")
      (node (ref "U1") (pin "41") (pinfunction "PC6_41") (pintype "input+no_connect"))
    )
    (net (code "68") (name "unconnected-(U1-PC7-Pad42)") (class "Default")
      (node (ref "U1") (pin "42") (pinfunction "PC7_42") (pintype "input+no_connect"))
    )
    (net (code "69") (name "unconnected-(U1-PD0-Pad25)") (class "Default")
      (node (ref "U1") (pin "25") (pinfunction "PD0_25") (pintype "input+no_connect"))
    )
    (net (code "70") (name "unconnected-(U1-PD1-Pad26)") (class "Default")
      (node (ref "U1") (pin "26") (pinfunction "PD1_26") (pintype "input+no_connect"))
    )
    (net (code "71") (name "unconnected-(U1-PD2-Pad27)") (class "Default")
      (node (ref "U1") (pin "27") (pinfunction "PD2_27") (pintype "input+no_connect"))
    )
    (net (code "72") (name "unconnected-(U1-PD3-Pad28)") (class "Default")
      (node (ref "U1") (pin "28") (pinfunction "PD3_28") (pintype "input+no_connect"))
    )
    (net (code "73") (name "unconnected-(U1-PD4-Pad29)") (class "Default")
      (node (ref "U1") (pin "29") (pinfunction "PD4_29") (pintype "input+no_connect"))
    )
    (net (code "74") (name "unconnected-(U1-PD5-Pad30)") (class "Default")
      (node (ref "U1") (pin "30") (pinfunction "PD5_30") (pintype "input+no_connect"))
    )
    (net (code "75") (name "unconnected-(U1-PD6-Pad31)") (class "Default")
      (node (ref "U1") (pin "31") (pinfunction "PD6_31") (pintype "input+no_connect"))
    )
    (net (code "76") (name "unconnected-(U1-PD7-Pad32)") (class "Default")
      (node (ref "U1") (pin "32") (pinfunction "PD7_32") (pintype "input+no_connect"))
    )
    (net (code "77") (name "unconnected-(U1-PE0-Pad33)") (class "Default")
      (node (ref "U1") (pin "33") (pinfunction "PE0_33") (pintype "input+no_connect"))
    )
    (net (code "78") (name "unconnected-(U1-PE1-Pad34)") (class "Default")
      (node (ref "U1") (pin "34") (pinfunction "PE1_34") (pintype "input+no_connect"))
    )
    (net (code "79") (name "unconnected-(U1-PE3-Pad9)") (class "Default")
      (node (ref "U1") (pin "9") (pinfunction "PE3_9") (pintype "input+no_connect"))
    )
    (net (code "80") (name "unconnected-(U1-PE4-Pad18)") (class "Default")
      (node (ref "U1") (pin "18") (pinfunction "PE4_18") (pintype "input+no_connect"))
    )
    (net (code "81") (name "unconnected-(U1-PE5-Pad19)") (class "Default")
      (node (ref "U1") (pin "19") (pinfunction "PE5_19") (pintype "input+no_connect"))
    )
    (net (code "82") (name "unconnected-(U1-PE6-Pad1)") (class "Default")
      (node (ref "U1") (pin "1") (pinfunction "PE6_1") (pintype "input+no_connect"))
    )
    (net (code "83") (name "unconnected-(U1-PE7-Pad2)") (class "Default")
      (node (ref "U1") (pin "2") (pinfunction "PE7_2") (pintype "input+no_connect"))
    )
  )
)
